# regulator_5v.net
KiCad netlist of a schematic drawn in EAGLE
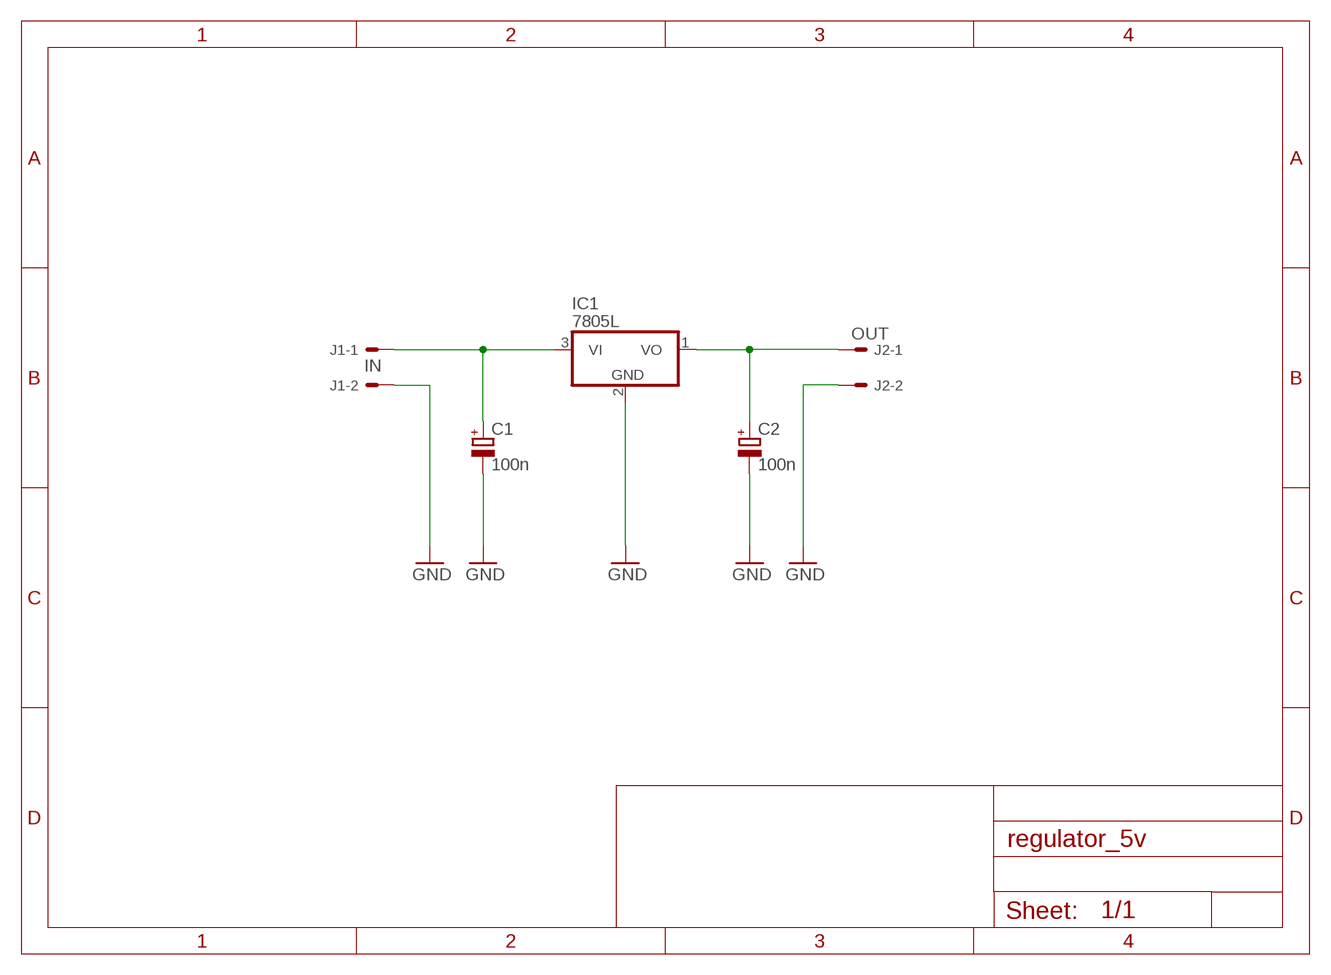
[diagram p0: schematic, sheet 1]

(export (version "E")
  (design (tool "Eeschema 10.0.6"))
  (components
    (comp (ref "C1")
      (value "100n")
      (footprint "eagle-import:TT2D5")
      (libsource (lib "eagle-import") (part "CPOL-EUTT2D5"))
    )
    (comp (ref "C2")
      (value "100n")
      (footprint "eagle-import:TT2D5")
      (libsource (lib "eagle-import") (part "CPOL-EUTT2D5"))
    )
    (comp (ref "IC1")
      (value "7805L")
      (footprint "eagle-import:TO92")
      (libsource (lib "eagle-import") (part "78L05"))
    )
    (comp (ref "J1")
      (value "IN")
      (footprint "eagle-import:6410-02")
      (libsource (lib "eagle-import") (part "22-?-0227-2021"))
    )
    (comp (ref "J2")
      (value "OUT")
      (footprint "eagle-import:6410-02")
      (libsource (lib "eagle-import") (part "22-?-0227-2021"))
    )
  )
  (nets
    (net (code "1") (name "GND") (class "Default")
      (node (ref "C1") (pin "-") (pinfunction "-_-") (pintype "passive"))
      (node (ref "C2") (pin "-") (pinfunction "-_-") (pintype "passive"))
      (node (ref "IC1") (pin "2") (pinfunction "GND_2") (pintype "passive"))
      (node (ref "J1") (pin "2") (pinfunction "S_2") (pintype "passive"))
      (node (ref "J2") (pin "2") (pinfunction "S_2") (pintype "passive"))
    )
    (net (code "2") (name "Net-(IC1-VI)") (class "Default")
      (node (ref "C1") (pin "+") (pinfunction "+_+") (pintype "passive"))
      (node (ref "IC1") (pin "3") (pinfunction "VI_3") (pintype "input"))
      (node (ref "J1") (pin "1") (pinfunction "S_1") (pintype "passive"))
    )
    (net (code "3") (name "Net-(IC1-VO)") (class "Default")
      (node (ref "C2") (pin "+") (pinfunction "+_+") (pintype "passive"))
      (node (ref "IC1") (pin "1") (pinfunction "VO_1") (pintype "passive"))
      (node (ref "J2") (pin "1") (pinfunction "S_1") (pintype "passive"))
    )
  )
)
